# VCF-LP-BP-HP_v4.net
KiCad netlist of a schematic drawn in EAGLE
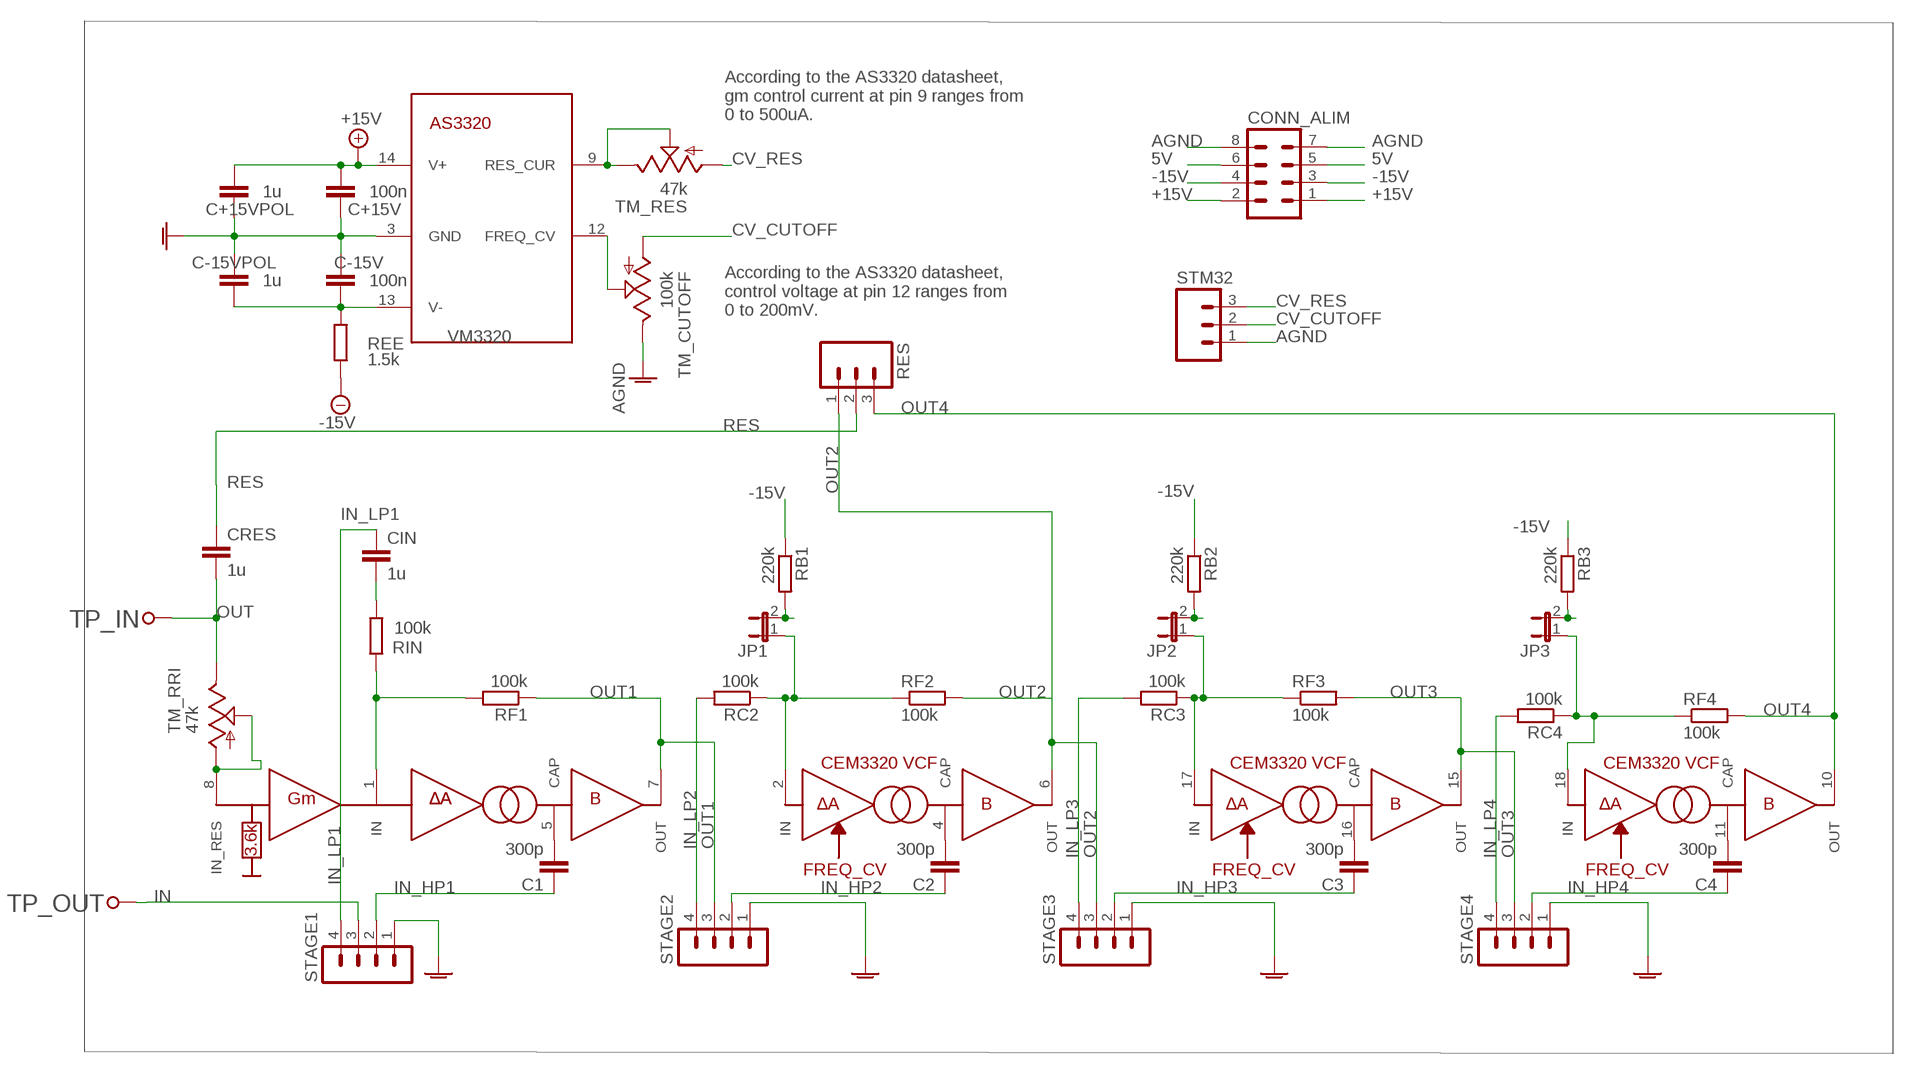
[diagram p0: schematic, sheet 1]

(export (version "E")
  (design (tool "Eeschema 10.0.6"))
  (components
    (comp (ref "C+15V")
      (value "100n")
      (footprint "eagle-import:C050-050X075")
      (libsource (lib "eagle-import") (part "C-EU050-050X075"))
    )
    (comp (ref "C+15VPOL")
      (value "1u")
      (footprint "eagle-import:C050-050X075")
      (libsource (lib "eagle-import") (part "C-EU050-050X075"))
    )
    (comp (ref "C-15V")
      (value "100n")
      (footprint "eagle-import:C050-050X075")
      (libsource (lib "eagle-import") (part "C-EU050-050X075"))
    )
    (comp (ref "C-15VPOL")
      (value "1u")
      (footprint "eagle-import:C050-050X075")
      (libsource (lib "eagle-import") (part "C-EU050-050X075"))
    )
    (comp (ref "C1")
      (value "300p")
      (footprint "eagle-import:C050-030X075")
      (libsource (lib "eagle-import") (part "C-EU050-030X075"))
    )
    (comp (ref "C2")
      (value "300p")
      (footprint "eagle-import:C075-032X103")
      (libsource (lib "eagle-import") (part "C-EU075-032X103"))
    )
    (comp (ref "C3")
      (value "300p")
      (footprint "eagle-import:C050-030X075")
      (libsource (lib "eagle-import") (part "C-EU050-030X075"))
    )
    (comp (ref "C4")
      (value "300p")
      (footprint "eagle-import:C050-030X075")
      (libsource (lib "eagle-import") (part "C-EU050-030X075"))
    )
    (comp (ref "CIN")
      (value "1u")
      (footprint "eagle-import:C050-030X075")
      (libsource (lib "eagle-import") (part "C-EU050-030X075"))
    )
    (comp (ref "CONN_ALIM")
      (value "MA04-2")
      (footprint "eagle-import:MA04-2")
      (libsource (lib "eagle-import") (part "MA04-2"))
    )
    (comp (ref "CRES")
      (value "1u")
      (footprint "eagle-import:C050-030X075")
      (libsource (lib "eagle-import") (part "C-EU050-030X075"))
    )
    (comp (ref "JP1")
      (value "JP1E")
      (footprint "eagle-import:JP1")
      (libsource (lib "eagle-import") (part "JP1E"))
    )
    (comp (ref "JP2")
      (value "JP1E")
      (footprint "eagle-import:JP1")
      (libsource (lib "eagle-import") (part "JP1E"))
    )
    (comp (ref "JP3")
      (value "JP1E")
      (footprint "eagle-import:JP1")
      (libsource (lib "eagle-import") (part "JP1E"))
    )
    (comp (ref "RB1")
      (value "220k")
      (footprint "eagle-import:0204_7")
      (libsource (lib "eagle-import") (part "R-EU_0204/7"))
    )
    (comp (ref "RB2")
      (value "220k")
      (footprint "eagle-import:0204_7")
      (libsource (lib "eagle-import") (part "R-EU_0204/7"))
    )
    (comp (ref "RB3")
      (value "220k")
      (footprint "eagle-import:0204_7")
      (libsource (lib "eagle-import") (part "R-EU_0204/7"))
    )
    (comp (ref "RC2")
      (value "100k")
      (footprint "eagle-import:0204_7")
      (libsource (lib "eagle-import") (part "R-EU_0204/7"))
    )
    (comp (ref "RC3")
      (value "100k")
      (footprint "eagle-import:0204_7")
      (libsource (lib "eagle-import") (part "R-EU_0204/7"))
    )
    (comp (ref "RC4")
      (value "100k")
      (footprint "eagle-import:0204_7")
      (libsource (lib "eagle-import") (part "R-EU_0204/7"))
    )
    (comp (ref "REE")
      (value "1.5k")
      (footprint "eagle-import:0207_7")
      (libsource (lib "eagle-import") (part "R-EU_0207/7"))
    )
    (comp (ref "RES")
      (value "MA03")
      (footprint "eagle-import:03P")
      (libsource (lib "eagle-import") (part "MA03"))
    )
    (comp (ref "RF1")
      (value "100k")
      (footprint "eagle-import:0204_7")
      (libsource (lib "eagle-import") (part "R-EU_0204/7"))
    )
    (comp (ref "RF2")
      (value "100k")
      (footprint "eagle-import:0204_7")
      (libsource (lib "eagle-import") (part "R-EU_0204/7"))
    )
    (comp (ref "RF3")
      (value "100k")
      (footprint "eagle-import:0204_7")
      (libsource (lib "eagle-import") (part "R-EU_0204/7"))
    )
    (comp (ref "RF4")
      (value "100k")
      (footprint "eagle-import:0204_7")
      (libsource (lib "eagle-import") (part "R-EU_0204/7"))
    )
    (comp (ref "RIN")
      (value "100k")
      (footprint "eagle-import:0204_7")
      (libsource (lib "eagle-import") (part "R-EU_0204/7"))
    )
    (comp (ref "STAGE1")
      (value "MA04-1")
      (footprint "eagle-import:MA04-1")
      (libsource (lib "eagle-import") (part "MA04-1"))
    )
    (comp (ref "STAGE2")
      (value "MA04-1")
      (footprint "eagle-import:MA04-1")
      (libsource (lib "eagle-import") (part "MA04-1"))
    )
    (comp (ref "STAGE3")
      (value "MA04-1")
      (footprint "eagle-import:MA04-1")
      (libsource (lib "eagle-import") (part "MA04-1"))
    )
    (comp (ref "STAGE4")
      (value "MA04-1")
      (footprint "eagle-import:MA04-1")
      (libsource (lib "eagle-import") (part "MA04-1"))
    )
    (comp (ref "STM32")
      (value "MA03")
      (footprint "eagle-import:03P")
      (libsource (lib "eagle-import") (part "MA03"))
    )
    (comp (ref "TM_CUTOFF")
      (value "100k")
      (footprint "eagle-import:6MM")
      (libsource (lib "eagle-import") (part "TRIM"))
    )
    (comp (ref "TM_RES")
      (value "47k")
      (footprint "eagle-import:6MM")
      (libsource (lib "eagle-import") (part "TRIM"))
    )
    (comp (ref "TM_RRI")
      (value "47k")
      (footprint "eagle-import:6MM")
      (libsource (lib "eagle-import") (part "TRIM"))
    )
    (comp (ref "TP_IN")
      (value "TESTPOINT")
      (footprint "eagle-import:TESTPOINT_63")
      (libsource (lib "eagle-import") (part "TESTPOINT"))
    )
    (comp (ref "TP_OUT")
      (value "TESTPOINT")
      (footprint "eagle-import:TESTPOINT_63")
      (libsource (lib "eagle-import") (part "TESTPOINT"))
    )
    (comp (ref "VCF")
      (value "AS3320")
      (footprint "eagle-import:DIL18")
      (libsource (lib "eagle-import") (part "AS3320"))
    )
  )
  (nets
    (net (code "1") (name "+15V") (class "Default")
      (node (ref "C+15V") (pin "2") (pinfunction "2_2") (pintype "passive"))
      (node (ref "C+15VPOL") (pin "2") (pinfunction "2_2") (pintype "passive"))
      (node (ref "CONN_ALIM") (pin "1") (pinfunction "1_1") (pintype "passive"))
      (node (ref "CONN_ALIM") (pin "2") (pinfunction "2_2") (pintype "passive"))
      (node (ref "VCF") (pin "14") (pinfunction "V+_14") (pintype "bidirectional"))
    )
    (net (code "2") (name "-15V") (class "Default")
      (node (ref "CONN_ALIM") (pin "3") (pinfunction "3_3") (pintype "passive"))
      (node (ref "CONN_ALIM") (pin "4") (pinfunction "4_4") (pintype "passive"))
      (node (ref "RB1") (pin "1") (pinfunction "1_1") (pintype "passive"))
      (node (ref "RB2") (pin "1") (pinfunction "1_1") (pintype "passive"))
      (node (ref "RB3") (pin "1") (pinfunction "1_1") (pintype "passive"))
      (node (ref "REE") (pin "1") (pinfunction "1_1") (pintype "passive"))
    )
    (net (code "3") (name "/5V") (class "Default")
      (node (ref "CONN_ALIM") (pin "5") (pinfunction "5_5") (pintype "passive"))
      (node (ref "CONN_ALIM") (pin "6") (pinfunction "6_6") (pintype "passive"))
    )
    (net (code "4") (name "/CV_CUTOFF") (class "Default")
      (node (ref "STM32") (pin "2") (pinfunction "2_2") (pintype "passive"))
      (node (ref "TM_CUTOFF") (pin "A") (pinfunction "A_A") (pintype "passive"))
    )
    (net (code "5") (name "/CV_RES") (class "Default")
      (node (ref "STM32") (pin "3") (pinfunction "3_3") (pintype "passive"))
      (node (ref "TM_RES") (pin "A") (pinfunction "A_A") (pintype "passive"))
    )
    (net (code "6") (name "/IN") (class "Default")
      (node (ref "STAGE1") (pin "3") (pinfunction "3_3") (pintype "passive"))
      (node (ref "TP_OUT") (pin "P$1") (pinfunction "P$1_P$1") (pintype "passive"))
    )
    (net (code "7") (name "/IN_HP1") (class "Default")
      (node (ref "C1") (pin "1") (pinfunction "1_1") (pintype "passive"))
      (node (ref "STAGE1") (pin "2") (pinfunction "2_2") (pintype "passive"))
    )
    (net (code "8") (name "/IN_HP2") (class "Default")
      (node (ref "C2") (pin "1") (pinfunction "1_1") (pintype "passive"))
      (node (ref "STAGE2") (pin "2") (pinfunction "2_2") (pintype "passive"))
    )
    (net (code "9") (name "/IN_HP3") (class "Default")
      (node (ref "C3") (pin "1") (pinfunction "1_1") (pintype "passive"))
      (node (ref "STAGE3") (pin "2") (pinfunction "2_2") (pintype "passive"))
    )
    (net (code "10") (name "/IN_HP4") (class "Default")
      (node (ref "C4") (pin "1") (pinfunction "1_1") (pintype "passive"))
      (node (ref "STAGE4") (pin "2") (pinfunction "2_2") (pintype "passive"))
    )
    (net (code "11") (name "/IN_LP1") (class "Default")
      (node (ref "CIN") (pin "1") (pinfunction "1_1") (pintype "passive"))
      (node (ref "STAGE1") (pin "4") (pinfunction "4_4") (pintype "passive"))
    )
    (net (code "12") (name "/IN_LP2") (class "Default")
      (node (ref "RC2") (pin "2") (pinfunction "2_2") (pintype "passive"))
      (node (ref "STAGE2") (pin "4") (pinfunction "4_4") (pintype "passive"))
    )
    (net (code "13") (name "/IN_LP3") (class "Default")
      (node (ref "RC3") (pin "2") (pinfunction "2_2") (pintype "passive"))
      (node (ref "STAGE3") (pin "4") (pinfunction "4_4") (pintype "passive"))
    )
    (net (code "14") (name "/IN_LP4") (class "Default")
      (node (ref "RC4") (pin "2") (pinfunction "2_2") (pintype "passive"))
      (node (ref "STAGE4") (pin "4") (pinfunction "4_4") (pintype "passive"))
    )
    (net (code "15") (name "/OUT") (class "Default")
      (node (ref "CRES") (pin "2") (pinfunction "2_2") (pintype "passive"))
      (node (ref "TM_RRI") (pin "E") (pinfunction "E_E") (pintype "passive"))
      (node (ref "TP_IN") (pin "P$1") (pinfunction "P$1_P$1") (pintype "passive"))
    )
    (net (code "16") (name "/OUT1") (class "Default")
      (node (ref "RF1") (pin "1") (pinfunction "1_1") (pintype "passive"))
      (node (ref "STAGE2") (pin "3") (pinfunction "3_3") (pintype "passive"))
      (node (ref "VCF") (pin "7") (pinfunction "OUT_7") (pintype "bidirectional"))
    )
    (net (code "17") (name "/OUT2") (class "Default")
      (node (ref "RES") (pin "1") (pinfunction "1_1") (pintype "passive"))
      (node (ref "RF2") (pin "2") (pinfunction "2_2") (pintype "passive"))
      (node (ref "STAGE3") (pin "3") (pinfunction "3_3") (pintype "passive"))
      (node (ref "VCF") (pin "6") (pinfunction "OUT_6") (pintype "bidirectional"))
    )
    (net (code "18") (name "/OUT3") (class "Default")
      (node (ref "RF3") (pin "2") (pinfunction "2_2") (pintype "passive"))
      (node (ref "STAGE4") (pin "3") (pinfunction "3_3") (pintype "passive"))
      (node (ref "VCF") (pin "15") (pinfunction "OUT_15") (pintype "bidirectional"))
    )
    (net (code "19") (name "/OUT4") (class "Default")
      (node (ref "RES") (pin "3") (pinfunction "3_3") (pintype "passive"))
      (node (ref "RF4") (pin "2") (pinfunction "2_2") (pintype "passive"))
      (node (ref "VCF") (pin "10") (pinfunction "OUT_10") (pintype "bidirectional"))
    )
    (net (code "20") (name "/RES") (class "Default")
      (node (ref "CRES") (pin "1") (pinfunction "1_1") (pintype "passive"))
      (node (ref "RES") (pin "2") (pinfunction "2_2") (pintype "passive"))
    )
    (net (code "21") (name "/VM3320") (class "Default")
      (node (ref "C-15V") (pin "1") (pinfunction "1_1") (pintype "passive"))
      (node (ref "C-15VPOL") (pin "1") (pinfunction "1_1") (pintype "passive"))
      (node (ref "REE") (pin "2") (pinfunction "2_2") (pintype "passive"))
      (node (ref "VCF") (pin "13") (pinfunction "V-_13") (pintype "bidirectional"))
    )
    (net (code "22") (name "AGND") (class "Default")
      (node (ref "C+15V") (pin "1") (pinfunction "1_1") (pintype "passive"))
      (node (ref "C+15VPOL") (pin "1") (pinfunction "1_1") (pintype "passive"))
      (node (ref "C-15V") (pin "2") (pinfunction "2_2") (pintype "passive"))
      (node (ref "C-15VPOL") (pin "2") (pinfunction "2_2") (pintype "passive"))
      (node (ref "CONN_ALIM") (pin "7") (pinfunction "7_7") (pintype "passive"))
      (node (ref "CONN_ALIM") (pin "8") (pinfunction "8_8") (pintype "passive"))
      (node (ref "STAGE1") (pin "1") (pinfunction "1_1") (pintype "passive"))
      (node (ref "STAGE2") (pin "1") (pinfunction "1_1") (pintype "passive"))
      (node (ref "STAGE3") (pin "1") (pinfunction "1_1") (pintype "passive"))
      (node (ref "STAGE4") (pin "1") (pinfunction "1_1") (pintype "passive"))
      (node (ref "STM32") (pin "1") (pinfunction "1_1") (pintype "passive"))
      (node (ref "TM_CUTOFF") (pin "E") (pinfunction "E_E") (pintype "passive"))
      (node (ref "VCF") (pin "3") (pinfunction "GND_3") (pintype "bidirectional"))
    )
    (net (code "23") (name "Net-(CIN-Pad2)") (class "Default")
      (node (ref "CIN") (pin "2") (pinfunction "2_2") (pintype "passive"))
      (node (ref "RIN") (pin "1") (pinfunction "1_1") (pintype "passive"))
    )
    (net (code "24") (name "Net-(JP1-Pad2)") (class "Default")
      (node (ref "JP1") (pin "2") (pinfunction "2_2") (pintype "passive"))
      (node (ref "RB1") (pin "2") (pinfunction "2_2") (pintype "passive"))
    )
    (net (code "25") (name "Net-(JP2-Pad2)") (class "Default")
      (node (ref "JP2") (pin "2") (pinfunction "2_2") (pintype "passive"))
      (node (ref "RB2") (pin "2") (pinfunction "2_2") (pintype "passive"))
    )
    (net (code "26") (name "Net-(JP3-Pad2)") (class "Default")
      (node (ref "JP3") (pin "2") (pinfunction "2_2") (pintype "passive"))
      (node (ref "RB3") (pin "2") (pinfunction "2_2") (pintype "passive"))
    )
    (net (code "27") (name "Net-(VCFA-CAP)") (class "Default")
      (node (ref "C1") (pin "2") (pinfunction "2_2") (pintype "passive"))
      (node (ref "VCF") (pin "5") (pinfunction "CAP_5") (pintype "bidirectional"))
    )
    (net (code "28") (name "Net-(VCFA-IN)") (class "Default")
      (node (ref "RF1") (pin "2") (pinfunction "2_2") (pintype "passive"))
      (node (ref "RIN") (pin "2") (pinfunction "2_2") (pintype "passive"))
      (node (ref "VCF") (pin "1") (pinfunction "IN_1") (pintype "bidirectional"))
    )
    (net (code "29") (name "Net-(VCFA-IN_RES)") (class "Default")
      (node (ref "TM_RRI") (pin "A") (pinfunction "A_A") (pintype "passive"))
      (node (ref "TM_RRI") (pin "S") (pinfunction "S_S") (pintype "passive"))
      (node (ref "VCF") (pin "8") (pinfunction "IN_RES_8") (pintype "bidirectional"))
    )
    (net (code "30") (name "Net-(VCFB-CAP)") (class "Default")
      (node (ref "C2") (pin "2") (pinfunction "2_2") (pintype "passive"))
      (node (ref "VCF") (pin "4") (pinfunction "CAP_4") (pintype "bidirectional"))
    )
    (net (code "31") (name "Net-(VCFB-IN)") (class "Default")
      (node (ref "JP1") (pin "1") (pinfunction "1_1") (pintype "passive"))
      (node (ref "RC2") (pin "1") (pinfunction "1_1") (pintype "passive"))
      (node (ref "RF2") (pin "1") (pinfunction "1_1") (pintype "passive"))
      (node (ref "VCF") (pin "2") (pinfunction "IN_2") (pintype "bidirectional"))
    )
    (net (code "32") (name "Net-(VCFC-CAP)") (class "Default")
      (node (ref "C4") (pin "2") (pinfunction "2_2") (pintype "passive"))
      (node (ref "VCF") (pin "11") (pinfunction "CAP_11") (pintype "bidirectional"))
    )
    (net (code "33") (name "Net-(VCFC-IN)") (class "Default")
      (node (ref "JP3") (pin "1") (pinfunction "1_1") (pintype "passive"))
      (node (ref "RC4") (pin "1") (pinfunction "1_1") (pintype "passive"))
      (node (ref "RF4") (pin "1") (pinfunction "1_1") (pintype "passive"))
      (node (ref "VCF") (pin "18") (pinfunction "IN_18") (pintype "bidirectional"))
    )
    (net (code "34") (name "Net-(VCFD-CAP)") (class "Default")
      (node (ref "C3") (pin "2") (pinfunction "2_2") (pintype "passive"))
      (node (ref "VCF") (pin "16") (pinfunction "CAP_16") (pintype "bidirectional"))
    )
    (net (code "35") (name "Net-(VCFD-IN)") (class "Default")
      (node (ref "JP2") (pin "1") (pinfunction "1_1") (pintype "passive"))
      (node (ref "RC3") (pin "1") (pinfunction "1_1") (pintype "passive"))
      (node (ref "RF3") (pin "1") (pinfunction "1_1") (pintype "passive"))
      (node (ref "VCF") (pin "17") (pinfunction "IN_17") (pintype "bidirectional"))
    )
    (net (code "36") (name "Net-(VCFE-FREQ_CV)") (class "Default")
      (node (ref "TM_CUTOFF") (pin "S") (pinfunction "S_S") (pintype "passive"))
      (node (ref "VCF") (pin "12") (pinfunction "FREQ_CV_12") (pintype "bidirectional"))
    )
    (net (code "37") (name "Net-(VCFE-RES_CUR)") (class "Default")
      (node (ref "TM_RES") (pin "E") (pinfunction "E_E") (pintype "passive"))
      (node (ref "TM_RES") (pin "S") (pinfunction "S_S") (pintype "passive"))
      (node (ref "VCF") (pin "9") (pinfunction "RES_CUR_9") (pintype "bidirectional"))
    )
  )
)
